# amplifier_v3.net
KiCad netlist of a schematic drawn in EAGLE
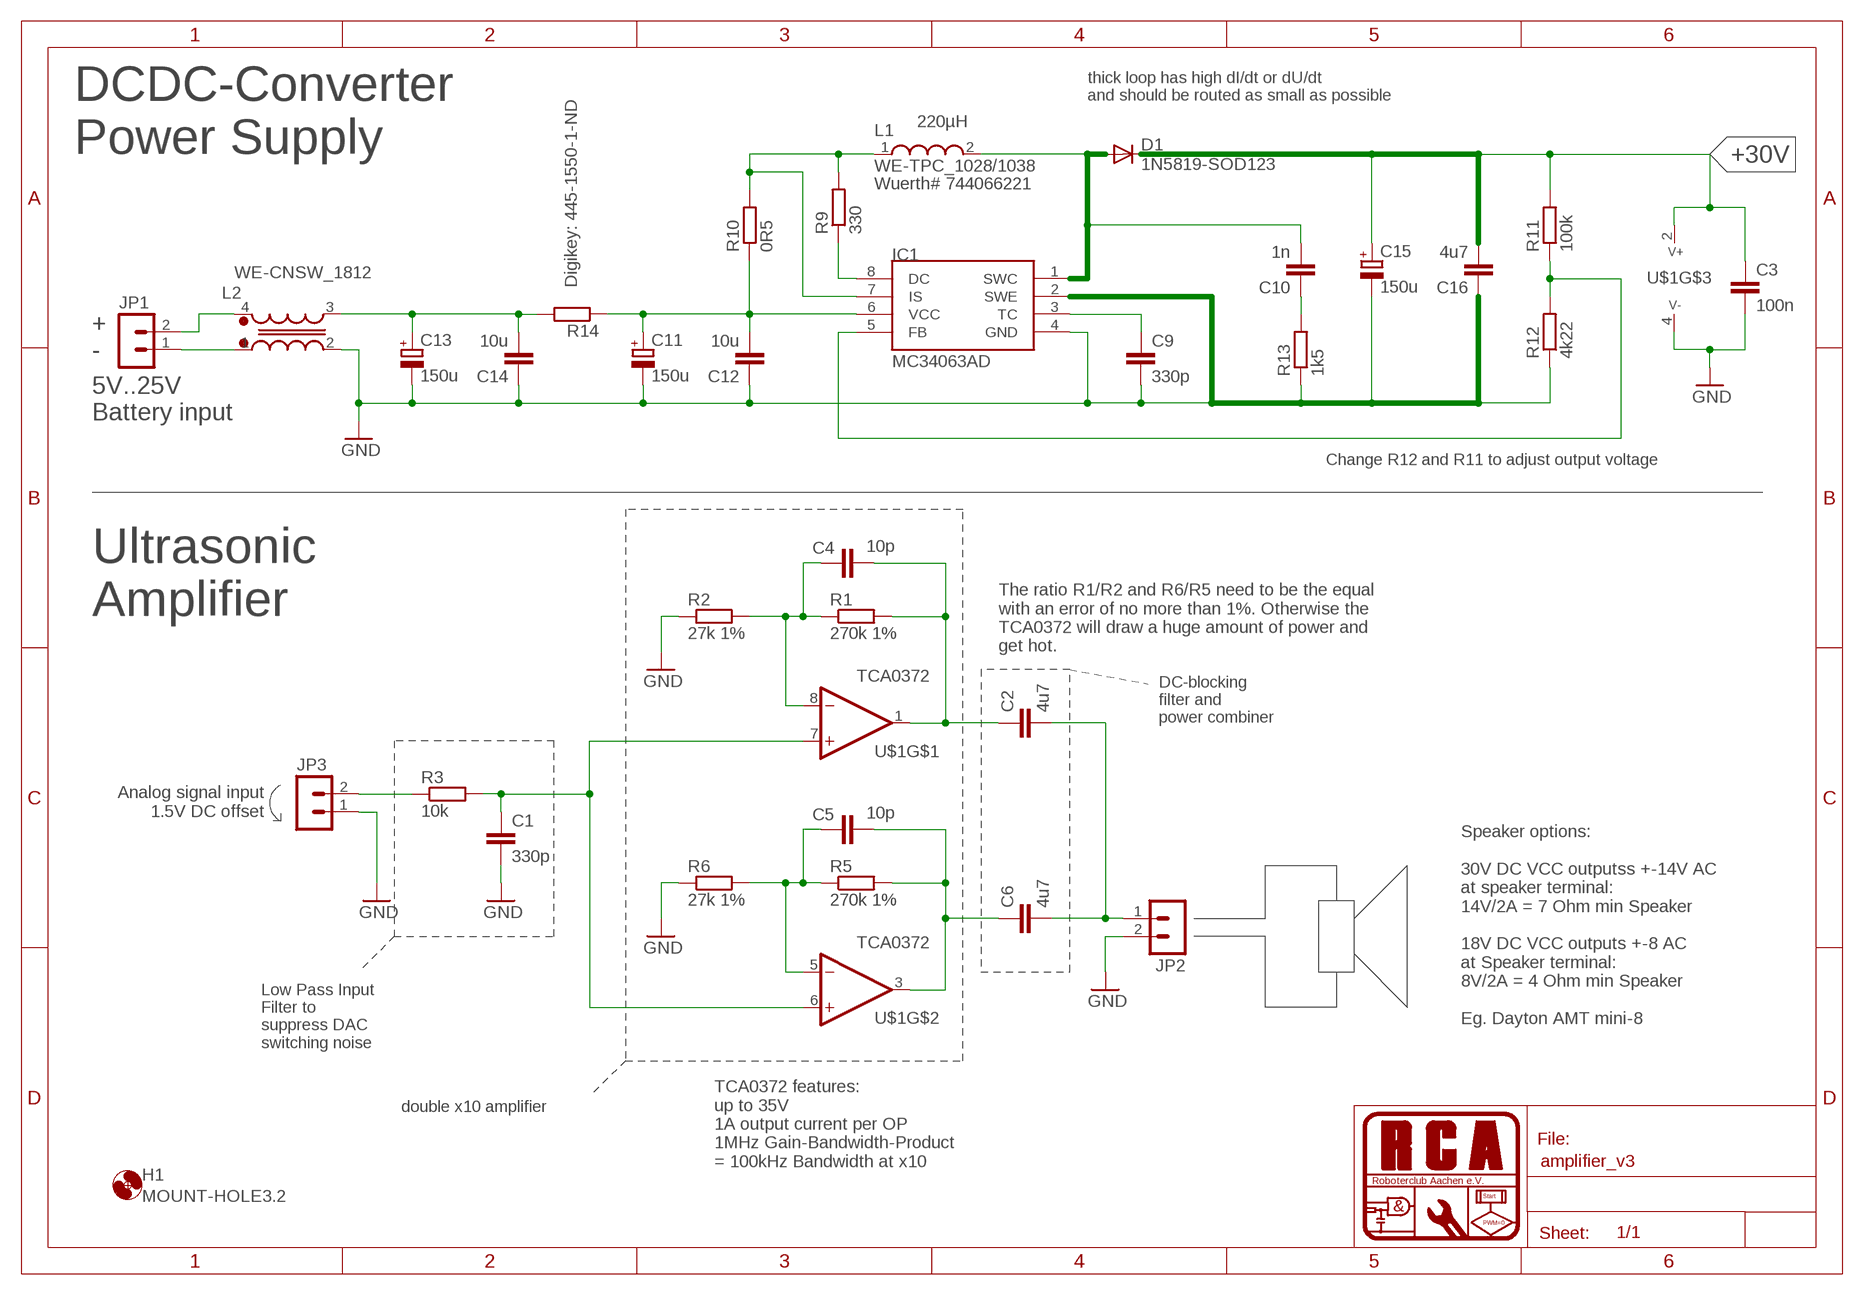
[diagram p0: schematic, sheet 1]

(export (version "E")
  (design (tool "Eeschema 10.0.6"))
  (components
    (comp (ref "C1")
      (value "330p")
      (footprint "eagle-import:C0603")
      (libsource (lib "eagle-import") (part "C-EUC0603"))
    )
    (comp (ref "C2")
      (value "4u7")
      (footprint "eagle-import:C0805")
      (libsource (lib "eagle-import") (part "C-EUC0805"))
    )
    (comp (ref "C3")
      (value "100n")
      (footprint "eagle-import:C0603")
      (libsource (lib "eagle-import") (part "C-EUC0603"))
    )
    (comp (ref "C4")
      (value "10p")
      (footprint "eagle-import:C0603")
      (libsource (lib "eagle-import") (part "C-EUC0603"))
    )
    (comp (ref "C5")
      (value "10p")
      (footprint "eagle-import:C0603")
      (libsource (lib "eagle-import") (part "C-EUC0603"))
    )
    (comp (ref "C6")
      (value "4u7")
      (footprint "eagle-import:C0805")
      (libsource (lib "eagle-import") (part "C-EUC0805"))
    )
    (comp (ref "C9")
      (value "330p")
      (footprint "eagle-import:C0603")
      (libsource (lib "eagle-import") (part "C-EUC0603"))
    )
    (comp (ref "C10")
      (value "1n")
      (footprint "eagle-import:C0603")
      (libsource (lib "eagle-import") (part "C-EUC0603"))
    )
    (comp (ref "C11")
      (value "150u")
      (footprint "eagle-import:E3,5-8")
      (libsource (lib "eagle-import") (part "CPOL-EUE3.5-8"))
    )
    (comp (ref "C12")
      (value "10u")
      (footprint "eagle-import:C0805")
      (libsource (lib "eagle-import") (part "C-EUC0805"))
    )
    (comp (ref "C13")
      (value "150u")
      (footprint "eagle-import:E3,5-8")
      (libsource (lib "eagle-import") (part "CPOL-EUE3.5-8"))
    )
    (comp (ref "C14")
      (value "10u")
      (footprint "eagle-import:C0805")
      (libsource (lib "eagle-import") (part "C-EUC0805"))
    )
    (comp (ref "C15")
      (value "150u")
      (footprint "eagle-import:E3,5-8")
      (libsource (lib "eagle-import") (part "CPOL-EUE3.5-8"))
    )
    (comp (ref "C16")
      (value "4u7")
      (footprint "eagle-import:C0805")
      (libsource (lib "eagle-import") (part "C-EUC0805"))
    )
    (comp (ref "D1")
      (value "1N5819-SOD123")
      (footprint "eagle-import:SOD123")
      (libsource (lib "eagle-import") (part "DIODE-SOD123"))
    )
    (comp (ref "H1")
      (value "MOUNT-HOLE3.2")
      (footprint "eagle-import:3,2")
      (libsource (lib "eagle-import") (part "MOUNT-HOLE3.2"))
    )
    (comp (ref "IC1")
      (value "MC34063AD")
      (footprint "eagle-import:SOIC8")
      (libsource (lib "eagle-import") (part "MC34063AD"))
    )
    (comp (ref "JP1")
      (value "PSS_2G")
      (footprint "eagle-import:22-23-2021")
      (libsource (lib "eagle-import") (part "PSS_2G"))
    )
    (comp (ref "JP2")
      (value "PSS_2G")
      (footprint "eagle-import:22-23-2021")
      (libsource (lib "eagle-import") (part "PSS_2G"))
    )
    (comp (ref "JP3")
      (value "PSS_2G")
      (footprint "eagle-import:22-23-2021")
      (libsource (lib "eagle-import") (part "PSS_2G"))
    )
    (comp (ref "L1")
      (value "WE-TPC_1028/1038")
      (footprint "eagle-import:WE-TPC_1028_1038")
      (libsource (lib "eagle-import") (part "WE-TPC_1028/1038"))
    )
    (comp (ref "L2")
      (value "WE-CNSW_1812")
      (footprint "eagle-import:WE-CNSW_1812")
      (libsource (lib "eagle-import") (part "WE-CNSW_1812"))
    )
    (comp (ref "R1")
      (value "270k 1%")
      (footprint "eagle-import:R0603")
      (libsource (lib "eagle-import") (part "R-EU_R0603"))
    )
    (comp (ref "R2")
      (value "27k 1%")
      (footprint "eagle-import:R0603")
      (libsource (lib "eagle-import") (part "R-EU_R0603"))
    )
    (comp (ref "R3")
      (value "10k")
      (footprint "eagle-import:R0603")
      (libsource (lib "eagle-import") (part "R-EU_R0603"))
    )
    (comp (ref "R5")
      (value "270k 1%")
      (footprint "eagle-import:R0603")
      (libsource (lib "eagle-import") (part "R-EU_R0603"))
    )
    (comp (ref "R6")
      (value "27k 1%")
      (footprint "eagle-import:R0603")
      (libsource (lib "eagle-import") (part "R-EU_R0603"))
    )
    (comp (ref "R9")
      (value "330")
      (footprint "eagle-import:R0603")
      (libsource (lib "eagle-import") (part "R-EU_R0603"))
    )
    (comp (ref "R10")
      (value "0R5")
      (footprint "eagle-import:R0603")
      (libsource (lib "eagle-import") (part "R-EU_R0603"))
    )
    (comp (ref "R11")
      (value "100k")
      (footprint "eagle-import:R0603")
      (libsource (lib "eagle-import") (part "R-EU_R0603"))
    )
    (comp (ref "R12")
      (value "4k22")
      (footprint "eagle-import:R0603")
      (libsource (lib "eagle-import") (part "R-EU_R0603"))
    )
    (comp (ref "R13")
      (value "1k5")
      (footprint "eagle-import:R0603")
      (libsource (lib "eagle-import") (part "R-EU_R0603"))
    )
    (comp (ref "R14")
      (value "Digikey: 445-1550-1-ND")
      (footprint "eagle-import:R0603")
      (libsource (lib "eagle-import") (part "R-EU_R0603"))
    )
    (comp (ref "U$1")
      (value "TCA0372")
      (footprint "eagle-import:DIL08")
      (libsource (lib "eagle-import") (part "TCA0372"))
    )
  )
  (nets
    (net (code "1") (name "+30V") (class "Default")
      (node (ref "C15") (pin "+") (pinfunction "+_+") (pintype "passive"))
      (node (ref "C16") (pin "2") (pinfunction "2_2") (pintype "passive"))
      (node (ref "C3") (pin "1") (pinfunction "1_1") (pintype "passive"))
      (node (ref "D1") (pin "C") (pinfunction "C_C") (pintype "passive"))
      (node (ref "R11") (pin "2") (pinfunction "2_2") (pintype "passive"))
      (node (ref "U$1") (pin "2") (pinfunction "V+_2") (pintype "power_in"))
    )
    (net (code "2") (name "GND") (class "Default")
      (node (ref "C1") (pin "2") (pinfunction "2_2") (pintype "passive"))
      (node (ref "C11") (pin "-") (pinfunction "-_-") (pintype "passive"))
      (node (ref "C12") (pin "1") (pinfunction "1_1") (pintype "passive"))
      (node (ref "C13") (pin "-") (pinfunction "-_-") (pintype "passive"))
      (node (ref "C14") (pin "1") (pinfunction "1_1") (pintype "passive"))
      (node (ref "C15") (pin "-") (pinfunction "-_-") (pintype "passive"))
      (node (ref "C16") (pin "1") (pinfunction "1_1") (pintype "passive"))
      (node (ref "C3") (pin "2") (pinfunction "2_2") (pintype "passive"))
      (node (ref "C9") (pin "2") (pinfunction "2_2") (pintype "passive"))
      (node (ref "IC1") (pin "2") (pinfunction "SWE_2") (pintype "passive"))
      (node (ref "IC1") (pin "4") (pinfunction "GND_4") (pintype "passive"))
      (node (ref "JP2") (pin "2") (pinfunction "2_2") (pintype "passive"))
      (node (ref "JP3") (pin "1") (pinfunction "1_1") (pintype "passive"))
      (node (ref "L2") (pin "2") (pinfunction "3_2") (pintype "passive"))
      (node (ref "R12") (pin "1") (pinfunction "1_1") (pintype "passive"))
      (node (ref "R13") (pin "1") (pinfunction "1_1") (pintype "passive"))
      (node (ref "R2") (pin "1") (pinfunction "1_1") (pintype "passive"))
      (node (ref "R6") (pin "1") (pinfunction "1_1") (pintype "passive"))
      (node (ref "U$1") (pin "4") (pinfunction "V-_4") (pintype "power_in"))
    )
    (net (code "3") (name "Net-(C2-Pad2)") (class "Default")
      (node (ref "C2") (pin "2") (pinfunction "2_2") (pintype "passive"))
      (node (ref "C6") (pin "2") (pinfunction "2_2") (pintype "passive"))
      (node (ref "JP2") (pin "1") (pinfunction "1_1") (pintype "passive"))
    )
    (net (code "4") (name "Net-(C10-Pad1)") (class "Default")
      (node (ref "C10") (pin "1") (pinfunction "1_1") (pintype "passive"))
      (node (ref "R13") (pin "2") (pinfunction "2_2") (pintype "passive"))
    )
    (net (code "5") (name "Net-(IC1-DC)") (class "Default")
      (node (ref "IC1") (pin "8") (pinfunction "DC_8") (pintype "passive"))
      (node (ref "R9") (pin "1") (pinfunction "1_1") (pintype "passive"))
    )
    (net (code "6") (name "Net-(IC1-FB)") (class "Default")
      (node (ref "IC1") (pin "5") (pinfunction "FB_5") (pintype "passive"))
      (node (ref "R11") (pin "1") (pinfunction "1_1") (pintype "passive"))
      (node (ref "R12") (pin "2") (pinfunction "2_2") (pintype "passive"))
    )
    (net (code "7") (name "Net-(IC1-IS)") (class "Default")
      (node (ref "IC1") (pin "7") (pinfunction "IS_7") (pintype "passive"))
      (node (ref "L1") (pin "1") (pinfunction "1_1") (pintype "passive"))
      (node (ref "R10") (pin "2") (pinfunction "2_2") (pintype "passive"))
      (node (ref "R9") (pin "2") (pinfunction "2_2") (pintype "passive"))
    )
    (net (code "8") (name "Net-(IC1-SWC)") (class "Default")
      (node (ref "C10") (pin "2") (pinfunction "2_2") (pintype "passive"))
      (node (ref "D1") (pin "A") (pinfunction "A_A") (pintype "passive"))
      (node (ref "IC1") (pin "1") (pinfunction "SWC_1") (pintype "passive"))
      (node (ref "L1") (pin "2") (pinfunction "2_2") (pintype "passive"))
    )
    (net (code "9") (name "Net-(IC1-TC)") (class "Default")
      (node (ref "C9") (pin "1") (pinfunction "1_1") (pintype "passive"))
      (node (ref "IC1") (pin "3") (pinfunction "TC_3") (pintype "passive"))
    )
    (net (code "10") (name "Net-(IC1-VCC)") (class "Default")
      (node (ref "C11") (pin "+") (pinfunction "+_+") (pintype "passive"))
      (node (ref "C12") (pin "2") (pinfunction "2_2") (pintype "passive"))
      (node (ref "IC1") (pin "6") (pinfunction "VCC_6") (pintype "passive"))
      (node (ref "R10") (pin "1") (pinfunction "1_1") (pintype "passive"))
      (node (ref "R14") (pin "1") (pinfunction "1_1") (pintype "passive"))
    )
    (net (code "11") (name "Net-(JP3-Pad2)") (class "Default")
      (node (ref "JP3") (pin "2") (pinfunction "2_2") (pintype "passive"))
      (node (ref "R3") (pin "1") (pinfunction "1_1") (pintype "passive"))
    )
    (net (code "12") (name "Net-(L2-1)") (class "Default")
      (node (ref "JP1") (pin "2") (pinfunction "2_2") (pintype "passive"))
      (node (ref "L2") (pin "4") (pinfunction "1_4") (pintype "passive"))
    )
    (net (code "13") (name "Net-(L2-2)") (class "Default")
      (node (ref "C13") (pin "+") (pinfunction "+_+") (pintype "passive"))
      (node (ref "C14") (pin "2") (pinfunction "2_2") (pintype "passive"))
      (node (ref "L2") (pin "3") (pinfunction "2_3") (pintype "passive"))
      (node (ref "R14") (pin "2") (pinfunction "2_2") (pintype "passive"))
    )
    (net (code "14") (name "Net-(L2-4)") (class "Default")
      (node (ref "JP1") (pin "1") (pinfunction "1_1") (pintype "passive"))
      (node (ref "L2") (pin "1") (pinfunction "4_1") (pintype "passive"))
    )
    (net (code "15") (name "Net-(U$1A-+IN)") (class "Default")
      (node (ref "C1") (pin "1") (pinfunction "1_1") (pintype "passive"))
      (node (ref "R3") (pin "2") (pinfunction "2_2") (pintype "passive"))
      (node (ref "U$1") (pin "6") (pinfunction "+IN_6") (pintype "input"))
      (node (ref "U$1") (pin "7") (pinfunction "+IN_7") (pintype "input"))
    )
    (net (code "16") (name "Net-(U$1A--IN)") (class "Default")
      (node (ref "C4") (pin "1") (pinfunction "1_1") (pintype "passive"))
      (node (ref "R1") (pin "1") (pinfunction "1_1") (pintype "passive"))
      (node (ref "R2") (pin "2") (pinfunction "2_2") (pintype "passive"))
      (node (ref "U$1") (pin "8") (pinfunction "-IN_8") (pintype "input"))
    )
    (net (code "17") (name "Net-(U$1A-OUT)") (class "Default")
      (node (ref "C2") (pin "1") (pinfunction "1_1") (pintype "passive"))
      (node (ref "C4") (pin "2") (pinfunction "2_2") (pintype "passive"))
      (node (ref "R1") (pin "2") (pinfunction "2_2") (pintype "passive"))
      (node (ref "U$1") (pin "1") (pinfunction "OUT_1") (pintype "output"))
    )
    (net (code "18") (name "Net-(U$1B--IN)") (class "Default")
      (node (ref "C5") (pin "1") (pinfunction "1_1") (pintype "passive"))
      (node (ref "R5") (pin "1") (pinfunction "1_1") (pintype "passive"))
      (node (ref "R6") (pin "2") (pinfunction "2_2") (pintype "passive"))
      (node (ref "U$1") (pin "5") (pinfunction "-IN_5") (pintype "input"))
    )
    (net (code "19") (name "Net-(U$1B-OUT)") (class "Default")
      (node (ref "C5") (pin "2") (pinfunction "2_2") (pintype "passive"))
      (node (ref "C6") (pin "1") (pinfunction "1_1") (pintype "passive"))
      (node (ref "R5") (pin "2") (pinfunction "2_2") (pintype "passive"))
      (node (ref "U$1") (pin "3") (pinfunction "OUT_3") (pintype "output"))
    )
  )
)
